# Audio_Filters.net
KiCad netlist of a schematic drawn in Altium Designer
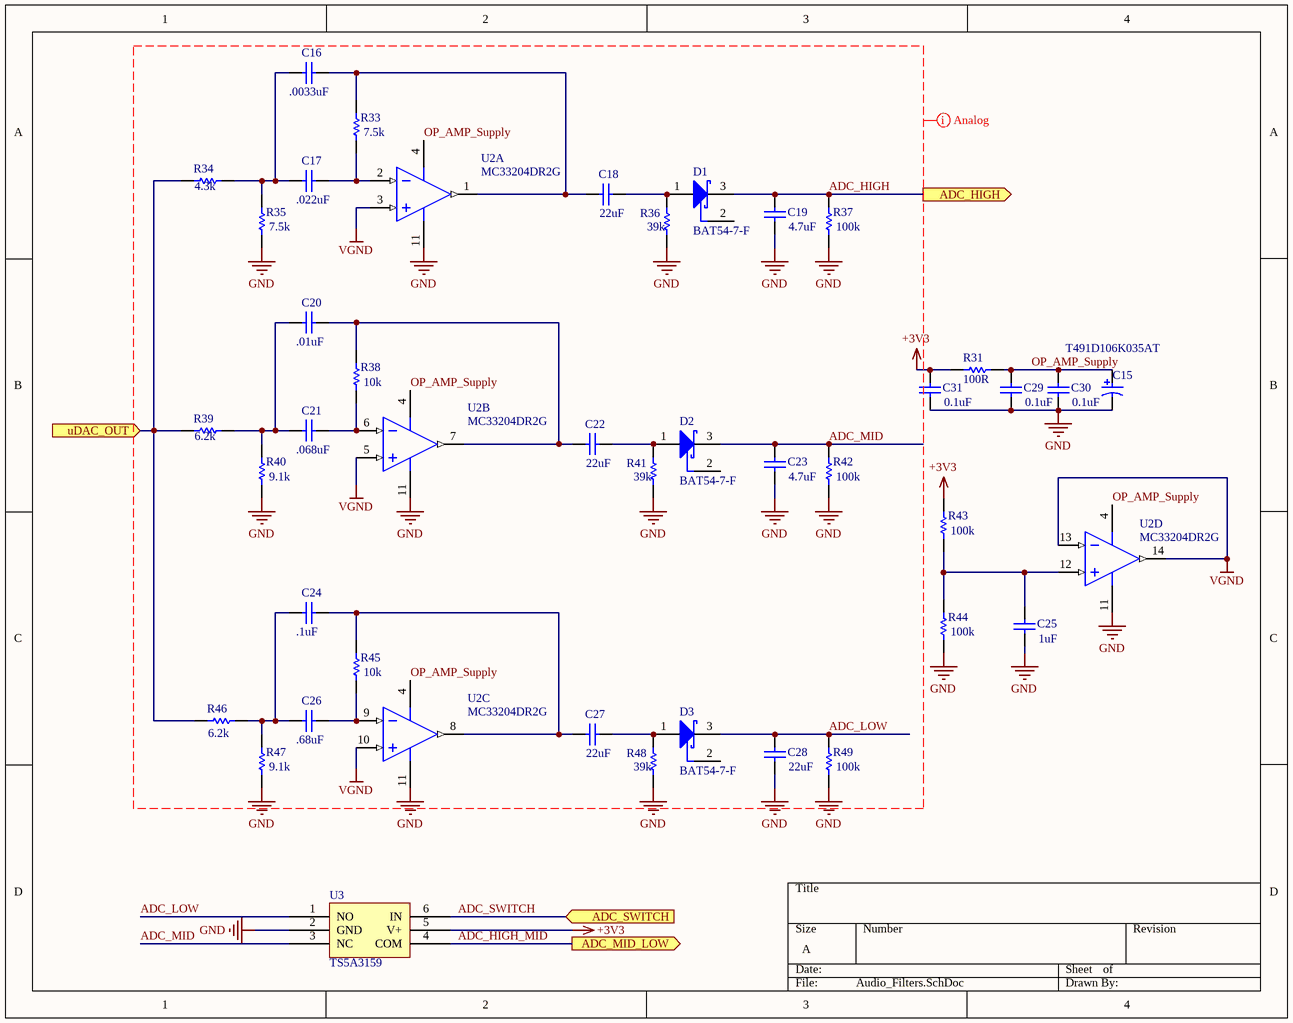
[diagram p0: Audio_Filters.SchDoc]

(export (version "E")
  (design (tool "Eeschema 10.0.6"))
  (components
    (comp (ref "C15")
      (value "T491D106K035AT")
      (footprint "KEMT-T491-D_L")
      (description "Tantalum Capacitor, 10 uF, +/- 10%, 35 V, -55 to 125 degC, 2-Pin SMD, RoHS, Tape and Reel")
      (fields (field (name "MANUFACTURER") "Kemet") (field (name "TOLERANCE") "20%"))
      (libsource (lib "Altium Content Vault") (part "CAP-P-2"))
    )
    (comp (ref "C16")
      (value ".0033uF")
      (footprint "CAPC0805(2012)145_L")
      (description "0805 (2012 Metric) Chip Capacitor")
      (fields (field (name "Comment") "CAP0805"))
      (libsource (lib "Altium Content Vault") (part "CAP_5"))
    )
    (comp (ref "C17")
      (value ".022uF")
      (footprint "CAPC0805(2012)145_L")
      (description "0805 (2012 Metric) Chip Capacitor")
      (fields (field (name "Comment") "CAP0805"))
      (libsource (lib "Altium Content Vault") (part "CAP_5"))
    )
    (comp (ref "C18")
      (value "22uF")
      (footprint "CAPC0805(2012)145_L")
      (description "0805 (2012 Metric) Chip Capacitor")
      (fields (field (name "Comment") "CAP0805"))
      (libsource (lib "Altium Content Vault") (part "CAP_5"))
    )
    (comp (ref "C19")
      (value "4.7uF")
      (footprint "CAPC0805(2012)145_L")
      (description "0805 (2012 Metric) Chip Capacitor")
      (fields (field (name "Comment") "CAP0805"))
      (libsource (lib "Altium Content Vault") (part "CAP_5"))
    )
    (comp (ref "C20")
      (value ".01uF")
      (footprint "CAPC0805(2012)145_L")
      (description "0805 (2012 Metric) Chip Capacitor")
      (fields (field (name "Comment") "CAP0805"))
      (libsource (lib "Altium Content Vault") (part "CAP_5"))
    )
    (comp (ref "C21")
      (value ".068uF")
      (footprint "CAPC0805(2012)145_L")
      (description "0805 (2012 Metric) Chip Capacitor")
      (fields (field (name "Comment") "CAP0805"))
      (libsource (lib "Altium Content Vault") (part "CAP_5"))
    )
    (comp (ref "C22")
      (value "22uF")
      (footprint "CAPC0805(2012)145_L")
      (description "0805 (2012 Metric) Chip Capacitor")
      (fields (field (name "Comment") "CAP0805"))
      (libsource (lib "Altium Content Vault") (part "CAP_5"))
    )
    (comp (ref "C23")
      (value "4.7uF")
      (footprint "CAPC0805(2012)145_L")
      (description "0805 (2012 Metric) Chip Capacitor")
      (fields (field (name "Comment") "CAP0805"))
      (libsource (lib "Altium Content Vault") (part "CAP_5"))
    )
    (comp (ref "C24")
      (value ".1uF")
      (footprint "CAPC0805(2012)145_L")
      (description "0805 (2012 Metric) Chip Capacitor")
      (fields (field (name "Comment") "CAP0805"))
      (libsource (lib "Altium Content Vault") (part "CAP_5"))
    )
    (comp (ref "C25")
      (value "1uF")
      (footprint "CAPC0805(2012)145_L")
      (description "0805 (2012 Metric) Chip Capacitor")
      (fields (field (name "Comment") "CAP0805"))
      (libsource (lib "Altium Content Vault") (part "CAP_5"))
    )
    (comp (ref "C26")
      (value ".68uF")
      (footprint "CAPC0805(2012)145_L")
      (description "0805 (2012 Metric) Chip Capacitor")
      (fields (field (name "Comment") "CAP0805"))
      (libsource (lib "Altium Content Vault") (part "CAP_5"))
    )
    (comp (ref "C27")
      (value "22uF")
      (footprint "CAPC0805(2012)145_L")
      (description "0805 (2012 Metric) Chip Capacitor")
      (fields (field (name "Comment") "CAP0805"))
      (libsource (lib "Altium Content Vault") (part "CAP_5"))
    )
    (comp (ref "C28")
      (value "22uF")
      (footprint "CAPC0805(2012)145_L")
      (description "0805 (2012 Metric) Chip Capacitor")
      (fields (field (name "Comment") "CAP0805"))
      (libsource (lib "Altium Content Vault") (part "CAP_5"))
    )
    (comp (ref "C29")
      (value "0.1uF")
      (footprint "CAPC0805(2012)145_L")
      (description "0805 (2012 Metric) Chip Capacitor")
      (fields (field (name "Comment") "CAP0805"))
      (libsource (lib "Altium Content Vault") (part "CAP_5"))
    )
    (comp (ref "C30")
      (value "0.1uF")
      (footprint "CAPC0805(2012)145_L")
      (description "0805 (2012 Metric) Chip Capacitor")
      (fields (field (name "Comment") "CAP0805"))
      (libsource (lib "Altium Content Vault") (part "CAP_5"))
    )
    (comp (ref "C31")
      (value "0.1uF")
      (footprint "CAPC0805(2012)145_L")
      (description "0805 (2012 Metric) Chip Capacitor")
      (fields (field (name "Comment") "CAP0805"))
      (libsource (lib "Altium Content Vault") (part "CAP_5"))
    )
    (comp (ref "D1")
      (value "BAT54-7-F")
      (footprint "DIOD-SOT23-3_V")
      (description "Schottky Diode, 30V ,200mW, SOT23-3")
      (fields (field (name "MANUFACTURER") "Diodes Inc"))
      (libsource (lib "Altium Content Vault") (part "DIOD-DSKY-A1K3-3"))
    )
    (comp (ref "D2")
      (value "BAT54-7-F")
      (footprint "DIOD-SOT23-3_V")
      (description "Schottky Diode, 30V ,200mW, SOT23-3")
      (fields (field (name "MANUFACTURER") "Diodes Inc"))
      (libsource (lib "Altium Content Vault") (part "DIOD-DSKY-A1K3-3"))
    )
    (comp (ref "D3")
      (value "BAT54-7-F")
      (footprint "DIOD-SOT23-3_V")
      (description "Schottky Diode, 30V ,200mW, SOT23-3")
      (fields (field (name "MANUFACTURER") "Diodes Inc"))
      (libsource (lib "Altium Content Vault") (part "DIOD-DSKY-A1K3-3"))
    )
    (comp (ref "R31")
      (value "100R")
      (footprint "RESC0805(2012)_L")
      (description "0805 (2012 Metric) Chip Resistor")
      (fields (field (name "Comment") "RES0805"))
      (libsource (lib "Altium Content Vault") (part "RES_3"))
    )
    (comp (ref "R33")
      (value "7.5k")
      (footprint "RESC0805(2012)_L")
      (description "0805 (2012 Metric) Chip Resistor")
      (fields (field (name "Comment") "RES0805"))
      (libsource (lib "Altium Content Vault") (part "RES_3"))
    )
    (comp (ref "R34")
      (value "4.3k")
      (footprint "RESC0805(2012)_L")
      (description "0805 (2012 Metric) Chip Resistor")
      (fields (field (name "Comment") "RES0805"))
      (libsource (lib "Altium Content Vault") (part "RES_3"))
    )
    (comp (ref "R35")
      (value "7.5k")
      (footprint "RESC0805(2012)_L")
      (description "0805 (2012 Metric) Chip Resistor")
      (fields (field (name "Comment") "RES0805"))
      (libsource (lib "Altium Content Vault") (part "RES_3"))
    )
    (comp (ref "R36")
      (value "39k")
      (footprint "RESC0805(2012)_L")
      (description "0805 (2012 Metric) Chip Resistor")
      (fields (field (name "Comment") "RES0805"))
      (libsource (lib "Altium Content Vault") (part "RES_3"))
    )
    (comp (ref "R37")
      (value "100k")
      (footprint "RESC0805(2012)_L")
      (description "0805 (2012 Metric) Chip Resistor")
      (fields (field (name "Comment") "RES0805"))
      (libsource (lib "Altium Content Vault") (part "RES_3"))
    )
    (comp (ref "R38")
      (value "10k")
      (footprint "RESC0805(2012)_L")
      (description "0805 (2012 Metric) Chip Resistor")
      (fields (field (name "Comment") "RES0805"))
      (libsource (lib "Altium Content Vault") (part "RES_3"))
    )
    (comp (ref "R39")
      (value "6.2k")
      (footprint "RESC0805(2012)_L")
      (description "0805 (2012 Metric) Chip Resistor")
      (fields (field (name "Comment") "RES0805"))
      (libsource (lib "Altium Content Vault") (part "RES_3"))
    )
    (comp (ref "R40")
      (value "9.1k")
      (footprint "RESC0805(2012)_L")
      (description "0805 (2012 Metric) Chip Resistor")
      (fields (field (name "Comment") "RES0805"))
      (libsource (lib "Altium Content Vault") (part "RES_3"))
    )
    (comp (ref "R41")
      (value "39k")
      (footprint "RESC0805(2012)_L")
      (description "0805 (2012 Metric) Chip Resistor")
      (fields (field (name "Comment") "RES0805"))
      (libsource (lib "Altium Content Vault") (part "RES_3"))
    )
    (comp (ref "R42")
      (value "100k")
      (footprint "RESC0805(2012)_L")
      (description "0805 (2012 Metric) Chip Resistor")
      (fields (field (name "Comment") "RES0805"))
      (libsource (lib "Altium Content Vault") (part "RES_3"))
    )
    (comp (ref "R43")
      (value "100k")
      (footprint "RESC0805(2012)_L")
      (description "0805 (2012 Metric) Chip Resistor")
      (fields (field (name "Comment") "RES0805"))
      (libsource (lib "Altium Content Vault") (part "RES_3"))
    )
    (comp (ref "R44")
      (value "100k")
      (footprint "RESC0805(2012)_L")
      (description "0805 (2012 Metric) Chip Resistor")
      (fields (field (name "Comment") "RES0805"))
      (libsource (lib "Altium Content Vault") (part "RES_3"))
    )
    (comp (ref "R45")
      (value "10k")
      (footprint "RESC0805(2012)_L")
      (description "0805 (2012 Metric) Chip Resistor")
      (fields (field (name "Comment") "RES0805"))
      (libsource (lib "Altium Content Vault") (part "RES_3"))
    )
    (comp (ref "R46")
      (value "6.2k")
      (footprint "RESC0805(2012)_L")
      (description "0805 (2012 Metric) Chip Resistor")
      (fields (field (name "Comment") "RES0805"))
      (libsource (lib "Altium Content Vault") (part "RES_3"))
    )
    (comp (ref "R47")
      (value "9.1k")
      (footprint "RESC0805(2012)_L")
      (description "0805 (2012 Metric) Chip Resistor")
      (fields (field (name "Comment") "RES0805"))
      (libsource (lib "Altium Content Vault") (part "RES_3"))
    )
    (comp (ref "R48")
      (value "39k")
      (footprint "RESC0805(2012)_L")
      (description "0805 (2012 Metric) Chip Resistor")
      (fields (field (name "Comment") "RES0805"))
      (libsource (lib "Altium Content Vault") (part "RES_3"))
    )
    (comp (ref "R49")
      (value "100k")
      (footprint "RESC0805(2012)_L")
      (description "0805 (2012 Metric) Chip Resistor")
      (fields (field (name "Comment") "RES0805"))
      (libsource (lib "Altium Content Vault") (part "RES_3"))
    )
    (comp (ref "U2")
      (value "MC33204DR2G")
      (footprint "ONSC-SOIC-14-751A-03_V")
      (fields (field (name "MANUFACTURER") "On Semiconductor"))
      (libsource (lib "Altium Content Vault") (part "ONSC-MC3XXX4_MC33079_NCV33274A-14"))
    )
    (comp (ref "U3")
      (value "TS5A3159")
      (footprint "SOT95P280X145-6N")
      (description "A 2 to 1 mux for reducing number of ADCs required")
      (libsource (lib "SpeakEasy") (part "TS5A3159"))
    )
  )
  (nets
    (net (code "1") (name "+3V3") (class "Default")
      (node (ref "C31") (pin "2") (pinfunction "2_2") (pintype "passive"))
      (node (ref "R31") (pin "2") (pinfunction "2_2") (pintype "passive"))
      (node (ref "R43") (pin "2") (pinfunction "2_2") (pintype "passive"))
      (node (ref "U3") (pin "5") (pinfunction "V+_5") (pintype "passive"))
    )
    (net (code "2") (name "/ADC_HIGH") (class "Default")
      (node (ref "C19") (pin "2") (pinfunction "2_2") (pintype "passive"))
      (node (ref "D1") (pin "3") (pinfunction "K_3") (pintype "passive"))
      (node (ref "R37") (pin "2") (pinfunction "2_2") (pintype "passive"))
    )
    (net (code "3") (name "/ADC_HIGH_MID") (class "Default")
      (node (ref "U3") (pin "4") (pinfunction "COM_4") (pintype "passive"))
    )
    (net (code "4") (name "/ADC_LOW") (class "Default")
      (node (ref "C28") (pin "2") (pinfunction "2_2") (pintype "passive"))
      (node (ref "D3") (pin "3") (pinfunction "K_3") (pintype "passive"))
      (node (ref "R49") (pin "2") (pinfunction "2_2") (pintype "passive"))
      (node (ref "U3") (pin "1") (pinfunction "NO_1") (pintype "passive"))
    )
    (net (code "5") (name "/ADC_MID") (class "Default")
      (node (ref "C23") (pin "2") (pinfunction "2_2") (pintype "passive"))
      (node (ref "D2") (pin "3") (pinfunction "K_3") (pintype "passive"))
      (node (ref "R42") (pin "2") (pinfunction "2_2") (pintype "passive"))
      (node (ref "U3") (pin "3") (pinfunction "NC_3") (pintype "passive"))
    )
    (net (code "6") (name "/ADC_SWITCH") (class "Default")
      (node (ref "U3") (pin "6") (pinfunction "IN_6") (pintype "passive"))
    )
    (net (code "7") (name "/OP_AMP_Supply") (class "Default")
      (node (ref "C15") (pin "1") (pinfunction "1_1") (pintype "passive"))
      (node (ref "C29") (pin "2") (pinfunction "2_2") (pintype "passive"))
      (node (ref "C30") (pin "2") (pinfunction "2_2") (pintype "passive"))
      (node (ref "R31") (pin "1") (pinfunction "1_1") (pintype "passive"))
      (node (ref "U2") (pin "4") (pinfunction "VCC_4") (pintype "power_in"))
    )
    (net (code "8") (name "/uDAC_OUT") (class "Default")
      (node (ref "R34") (pin "1") (pinfunction "1_1") (pintype "passive"))
      (node (ref "R39") (pin "1") (pinfunction "1_1") (pintype "passive"))
      (node (ref "R46") (pin "1") (pinfunction "1_1") (pintype "passive"))
    )
    (net (code "9") (name "GND") (class "Default")
      (node (ref "C15") (pin "2") (pinfunction "2_2") (pintype "passive"))
      (node (ref "C19") (pin "1") (pinfunction "1_1") (pintype "passive"))
      (node (ref "C23") (pin "1") (pinfunction "1_1") (pintype "passive"))
      (node (ref "C25") (pin "1") (pinfunction "1_1") (pintype "passive"))
      (node (ref "C28") (pin "1") (pinfunction "1_1") (pintype "passive"))
      (node (ref "C29") (pin "1") (pinfunction "1_1") (pintype "passive"))
      (node (ref "C30") (pin "1") (pinfunction "1_1") (pintype "passive"))
      (node (ref "C31") (pin "1") (pinfunction "1_1") (pintype "passive"))
      (node (ref "R35") (pin "2") (pinfunction "2_2") (pintype "passive"))
      (node (ref "R36") (pin "1") (pinfunction "1_1") (pintype "passive"))
      (node (ref "R37") (pin "1") (pinfunction "1_1") (pintype "passive"))
      (node (ref "R40") (pin "2") (pinfunction "2_2") (pintype "passive"))
      (node (ref "R41") (pin "1") (pinfunction "1_1") (pintype "passive"))
      (node (ref "R42") (pin "1") (pinfunction "1_1") (pintype "passive"))
      (node (ref "R44") (pin "1") (pinfunction "1_1") (pintype "passive"))
      (node (ref "R47") (pin "2") (pinfunction "2_2") (pintype "passive"))
      (node (ref "R48") (pin "1") (pinfunction "1_1") (pintype "passive"))
      (node (ref "R49") (pin "1") (pinfunction "1_1") (pintype "passive"))
      (node (ref "U2") (pin "11") (pinfunction "VEE_11") (pintype "power_in"))
      (node (ref "U3") (pin "2") (pinfunction "GND_2") (pintype "passive"))
    )
    (net (code "10") (name "Net-(C16-Pad1)") (class "Default")
      (node (ref "C16") (pin "1") (pinfunction "1_1") (pintype "passive"))
      (node (ref "C17") (pin "1") (pinfunction "1_1") (pintype "passive"))
      (node (ref "R34") (pin "2") (pinfunction "2_2") (pintype "passive"))
      (node (ref "R35") (pin "1") (pinfunction "1_1") (pintype "passive"))
    )
    (net (code "11") (name "Net-(C20-Pad1)") (class "Default")
      (node (ref "C20") (pin "1") (pinfunction "1_1") (pintype "passive"))
      (node (ref "C21") (pin "1") (pinfunction "1_1") (pintype "passive"))
      (node (ref "R39") (pin "2") (pinfunction "2_2") (pintype "passive"))
      (node (ref "R40") (pin "1") (pinfunction "1_1") (pintype "passive"))
    )
    (net (code "12") (name "Net-(C24-Pad1)") (class "Default")
      (node (ref "C24") (pin "1") (pinfunction "1_1") (pintype "passive"))
      (node (ref "C26") (pin "1") (pinfunction "1_1") (pintype "passive"))
      (node (ref "R46") (pin "2") (pinfunction "2_2") (pintype "passive"))
      (node (ref "R47") (pin "1") (pinfunction "1_1") (pintype "passive"))
    )
    (net (code "13") (name "Net-(D1-A)") (class "Default")
      (node (ref "C18") (pin "2") (pinfunction "2_2") (pintype "passive"))
      (node (ref "D1") (pin "1") (pinfunction "A_1") (pintype "passive"))
      (node (ref "R36") (pin "2") (pinfunction "2_2") (pintype "passive"))
    )
    (net (code "14") (name "Net-(D2-A)") (class "Default")
      (node (ref "C22") (pin "2") (pinfunction "2_2") (pintype "passive"))
      (node (ref "D2") (pin "1") (pinfunction "A_1") (pintype "passive"))
      (node (ref "R41") (pin "2") (pinfunction "2_2") (pintype "passive"))
    )
    (net (code "15") (name "Net-(D3-A)") (class "Default")
      (node (ref "C27") (pin "2") (pinfunction "2_2") (pintype "passive"))
      (node (ref "D3") (pin "1") (pinfunction "A_1") (pintype "passive"))
      (node (ref "R48") (pin "2") (pinfunction "2_2") (pintype "passive"))
    )
    (net (code "16") (name "Net-(U2A-IN1-)") (class "Default")
      (node (ref "C17") (pin "2") (pinfunction "2_2") (pintype "passive"))
      (node (ref "R33") (pin "2") (pinfunction "2_2") (pintype "passive"))
      (node (ref "U2") (pin "2") (pinfunction "IN1-_2") (pintype "input"))
    )
    (net (code "17") (name "Net-(U2A-OUT1)") (class "Default")
      (node (ref "C16") (pin "2") (pinfunction "2_2") (pintype "passive"))
      (node (ref "C18") (pin "1") (pinfunction "1_1") (pintype "passive"))
      (node (ref "R33") (pin "1") (pinfunction "1_1") (pintype "passive"))
      (node (ref "U2") (pin "1") (pinfunction "OUT1_1") (pintype "output"))
    )
    (net (code "18") (name "Net-(U2B-IN2-)") (class "Default")
      (node (ref "C21") (pin "2") (pinfunction "2_2") (pintype "passive"))
      (node (ref "R38") (pin "2") (pinfunction "2_2") (pintype "passive"))
      (node (ref "U2") (pin "6") (pinfunction "IN2-_6") (pintype "input"))
    )
    (net (code "19") (name "Net-(U2B-OUT2)") (class "Default")
      (node (ref "C20") (pin "2") (pinfunction "2_2") (pintype "passive"))
      (node (ref "C22") (pin "1") (pinfunction "1_1") (pintype "passive"))
      (node (ref "R38") (pin "1") (pinfunction "1_1") (pintype "passive"))
      (node (ref "U2") (pin "7") (pinfunction "OUT2_7") (pintype "output"))
    )
    (net (code "20") (name "Net-(U2C-IN3-)") (class "Default")
      (node (ref "C26") (pin "2") (pinfunction "2_2") (pintype "passive"))
      (node (ref "R45") (pin "2") (pinfunction "2_2") (pintype "passive"))
      (node (ref "U2") (pin "9") (pinfunction "IN3-_9") (pintype "input"))
    )
    (net (code "21") (name "Net-(U2C-OUT3)") (class "Default")
      (node (ref "C24") (pin "2") (pinfunction "2_2") (pintype "passive"))
      (node (ref "C27") (pin "1") (pinfunction "1_1") (pintype "passive"))
      (node (ref "R45") (pin "1") (pinfunction "1_1") (pintype "passive"))
      (node (ref "U2") (pin "8") (pinfunction "OUT3_8") (pintype "output"))
    )
    (net (code "22") (name "Net-(U2D-IN4+)") (class "Default")
      (node (ref "C25") (pin "2") (pinfunction "2_2") (pintype "passive"))
      (node (ref "R43") (pin "1") (pinfunction "1_1") (pintype "passive"))
      (node (ref "R44") (pin "2") (pinfunction "2_2") (pintype "passive"))
      (node (ref "U2") (pin "12") (pinfunction "IN4+_12") (pintype "input"))
    )
    (net (code "23") (name "VGND") (class "Default")
      (node (ref "U2") (pin "10") (pinfunction "IN3+_10") (pintype "input"))
      (node (ref "U2") (pin "13") (pinfunction "IN4-_13") (pintype "input"))
      (node (ref "U2") (pin "14") (pinfunction "OUT4_14") (pintype "output"))
      (node (ref "U2") (pin "3") (pinfunction "IN1+_3") (pintype "input"))
      (node (ref "U2") (pin "5") (pinfunction "IN2+_5") (pintype "input"))
    )
    (net (code "24") (name "unconnected-(D1-NC-Pad2)") (class "Default")
      (node (ref "D1") (pin "2") (pinfunction "NC_2") (pintype "passive"))
    )
    (net (code "25") (name "unconnected-(D1-Pad2)") (class "Default")
      (node (ref "D1") (pin "2") (pintype "passive"))
    )
    (net (code "26") (name "unconnected-(D2-NC-Pad2)") (class "Default")
      (node (ref "D2") (pin "2") (pinfunction "NC_2") (pintype "passive"))
    )
    (net (code "27") (name "unconnected-(D2-Pad2)") (class "Default")
      (node (ref "D2") (pin "2") (pintype "passive"))
    )
    (net (code "28") (name "unconnected-(D3-NC-Pad2)") (class "Default")
      (node (ref "D3") (pin "2") (pinfunction "NC_2") (pintype "passive"))
    )
    (net (code "29") (name "unconnected-(D3-Pad2)") (class "Default")
      (node (ref "D3") (pin "2") (pintype "passive"))
    )
  )
)
